# Heating_Controller.net
KiCad netlist of a schematic drawn in EAGLE
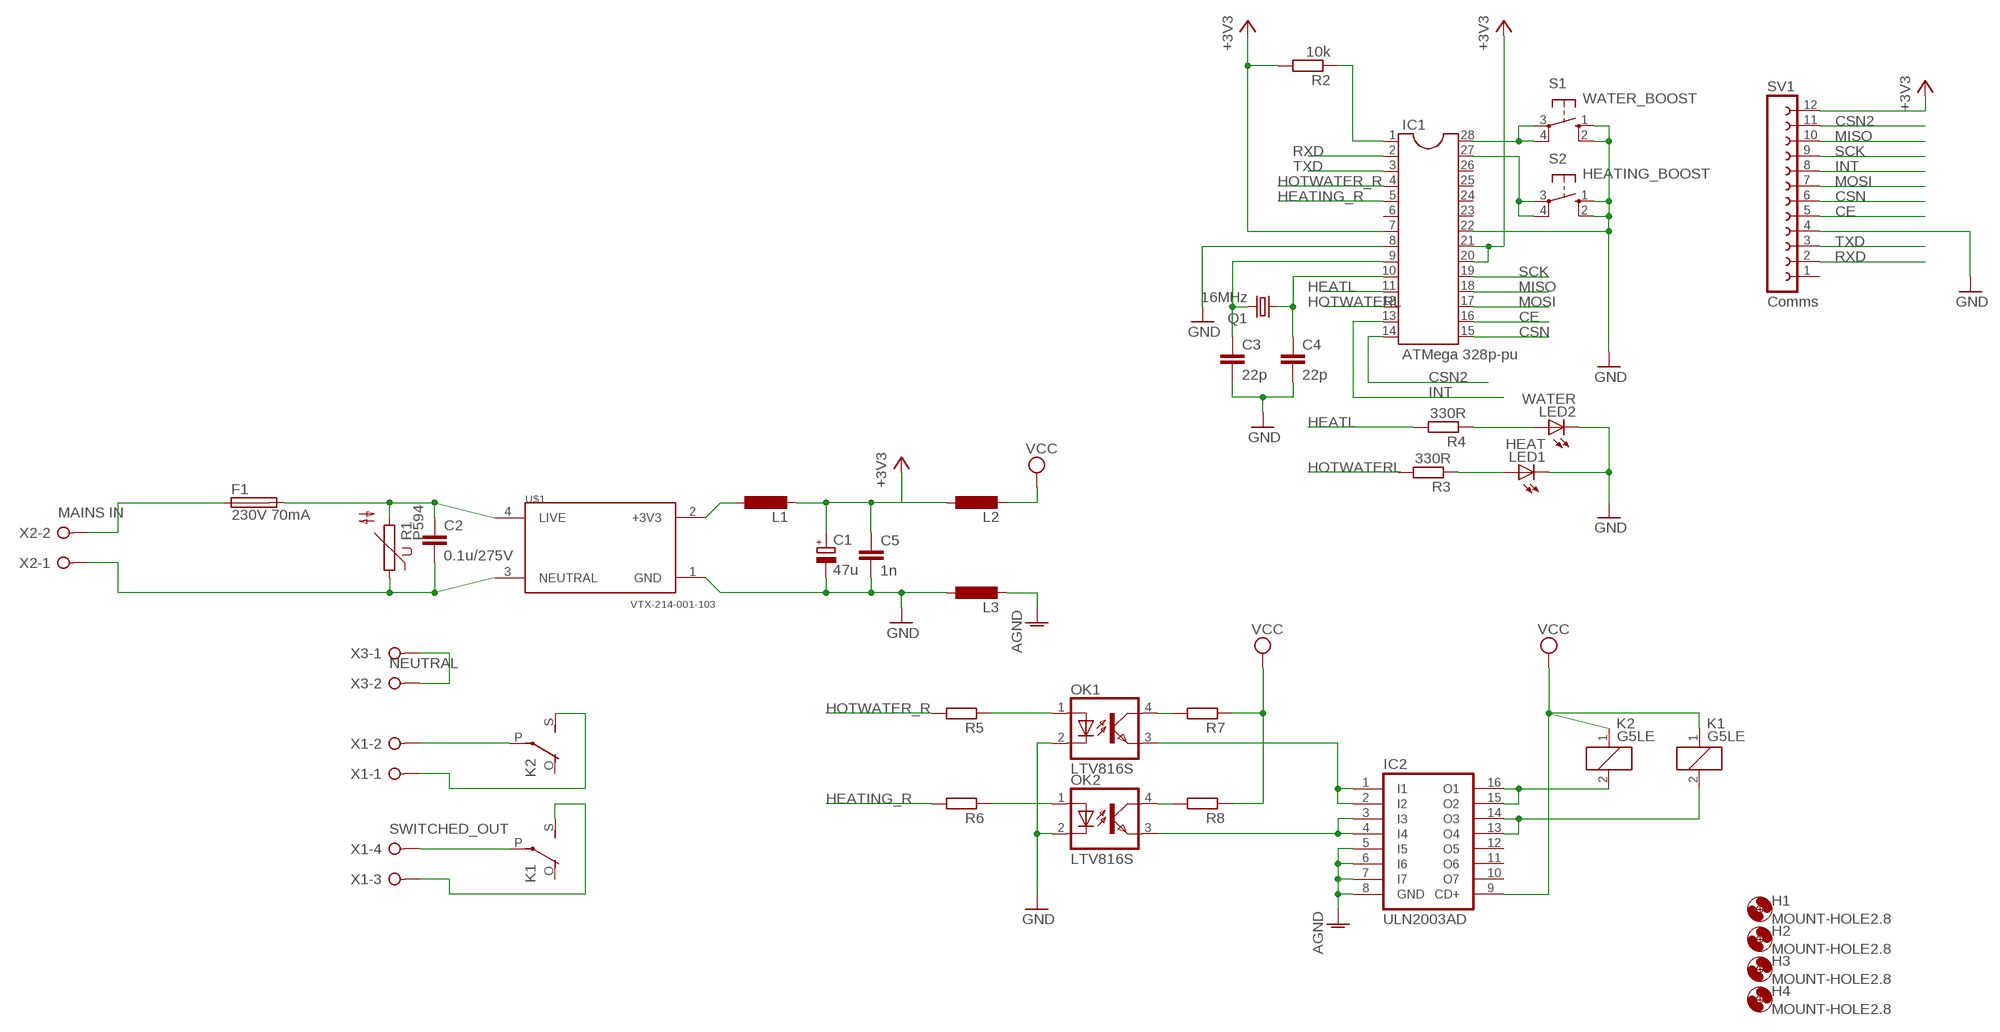
[diagram p0: schematic, sheet 1]

(export (version "E")
  (design (tool "Eeschema 10.0.6"))
  (components
    (comp (ref "C1")
      (value "47u")
      (footprint "eagle-import:E2,5-7")
      (libsource (lib "eagle-import") (part "CPOL-EUE2.5-7"))
    )
    (comp (ref "C2")
      (value "0.1u/275V")
      (footprint "eagle-import:C15B5")
      (libsource (lib "eagle-import") (part "C15/5"))
    )
    (comp (ref "C3")
      (value "22p")
      (footprint "eagle-import:C1206K")
      (libsource (lib "eagle-import") (part "C-EUC1206K"))
    )
    (comp (ref "C4")
      (value "22p")
      (footprint "eagle-import:C1206K")
      (libsource (lib "eagle-import") (part "C-EUC1206K"))
    )
    (comp (ref "C5")
      (value "1n")
      (footprint "eagle-import:C1206K")
      (libsource (lib "eagle-import") (part "C-EUC1206K"))
    )
    (comp (ref "F1")
      (value "230V 70mA")
      (footprint "eagle-import:SH22,5A")
      (fields (field (name "MPN") "0031.7701.11"))
      (libsource (lib "eagle-import") (part "SH22,5A"))
    )
    (comp (ref "H1")
      (value "MOUNT-HOLE2.8")
      (footprint "eagle-import:2,8")
      (libsource (lib "eagle-import") (part "MOUNT-HOLE2.8"))
    )
    (comp (ref "H2")
      (value "MOUNT-HOLE2.8")
      (footprint "eagle-import:2,8")
      (libsource (lib "eagle-import") (part "MOUNT-HOLE2.8"))
    )
    (comp (ref "H3")
      (value "MOUNT-HOLE2.8")
      (footprint "eagle-import:2,8")
      (libsource (lib "eagle-import") (part "MOUNT-HOLE2.8"))
    )
    (comp (ref "H4")
      (value "MOUNT-HOLE2.8")
      (footprint "eagle-import:2,8")
      (libsource (lib "eagle-import") (part "MOUNT-HOLE2.8"))
    )
    (comp (ref "IC1")
      (value "ATMega 328p-pu")
      (footprint "eagle-import:DIL28-3")
      (libsource (lib "eagle-import") (part "DIL28-3"))
    )
    (comp (ref "IC2")
      (value "ULN2003AD")
      (footprint "eagle-import:SO16")
      (libsource (lib "eagle-import") (part "ULN2003AD"))
    )
    (comp (ref "K1")
      (value "G5LE")
      (footprint "eagle-import:G5LE")
      (libsource (lib "eagle-import") (part "G5LE"))
    )
    (comp (ref "K2")
      (value "G5LE")
      (footprint "eagle-import:G5LE")
      (libsource (lib "eagle-import") (part "G5LE"))
    )
    (comp (ref "L1")
      (value "L-EUL3230M")
      (footprint "eagle-import:L3230M")
      (libsource (lib "eagle-import") (part "L-EUL3230M"))
    )
    (comp (ref "L2")
      (value "L-EUL3230M")
      (footprint "eagle-import:L3230M")
      (libsource (lib "eagle-import") (part "L-EUL3230M"))
    )
    (comp (ref "L3")
      (value "L-EUL3230M")
      (footprint "eagle-import:L3230M")
      (libsource (lib "eagle-import") (part "L-EUL3230M"))
    )
    (comp (ref "LED1")
      (value "HEAT")
      (footprint "eagle-import:LED5MM")
      (libsource (lib "eagle-import") (part "LED5MM"))
    )
    (comp (ref "LED2")
      (value "WATER")
      (footprint "eagle-import:LED5MM")
      (libsource (lib "eagle-import") (part "LED5MM"))
    )
    (comp (ref "OK1")
      (value "LTV816S")
      (footprint "eagle-import:SMD4")
      (libsource (lib "eagle-import") (part "LTV816S"))
    )
    (comp (ref "OK2")
      (value "LTV816S")
      (footprint "eagle-import:SMD4")
      (libsource (lib "eagle-import") (part "LTV816S"))
    )
    (comp (ref "Q1")
      (value "16MHz")
      (footprint "eagle-import:HC49_S")
      (libsource (lib "eagle-import") (part "CRYSTALHC49S"))
    )
    (comp (ref "R1")
      (value "P594")
      (footprint "eagle-import:P594")
      (libsource (lib "eagle-import") (part "P594"))
    )
    (comp (ref "R2")
      (value "10k")
      (footprint "eagle-import:R1206")
      (libsource (lib "eagle-import") (part "R-EU_R1206"))
    )
    (comp (ref "R3")
      (value "330R")
      (footprint "eagle-import:R1206")
      (libsource (lib "eagle-import") (part "R-EU_R1206"))
    )
    (comp (ref "R4")
      (value "330R")
      (footprint "eagle-import:R1206")
      (libsource (lib "eagle-import") (part "R-EU_R1206"))
    )
    (comp (ref "R5")
      (value "R-EU_R1206")
      (footprint "eagle-import:R1206")
      (libsource (lib "eagle-import") (part "R-EU_R1206"))
    )
    (comp (ref "R6")
      (value "R-EU_R1206")
      (footprint "eagle-import:R1206")
      (libsource (lib "eagle-import") (part "R-EU_R1206"))
    )
    (comp (ref "R7")
      (value "R-EU_R1206")
      (footprint "eagle-import:R1206")
      (libsource (lib "eagle-import") (part "R-EU_R1206"))
    )
    (comp (ref "R8")
      (value "R-EU_R1206")
      (footprint "eagle-import:R1206")
      (libsource (lib "eagle-import") (part "R-EU_R1206"))
    )
    (comp (ref "S1")
      (value "WATER_BOOST")
      (footprint "eagle-import:B3F-40XX")
      (fields (field (name "MF") "OMRON COMPONENTS USA") (field (name "MPN") "B3F-4000"))
      (libsource (lib "eagle-import") (part "40-XX"))
    )
    (comp (ref "S2")
      (value "HEATING_BOOST")
      (footprint "eagle-import:B3F-40XX")
      (fields (field (name "MF") "OMRON COMPONENTS USA") (field (name "MPN") "B3F-4000"))
      (libsource (lib "eagle-import") (part "40-XX"))
    )
    (comp (ref "SV1")
      (value "Comms")
      (footprint "eagle-import:FE12W")
      (libsource (lib "eagle-import") (part "FE12W"))
    )
    (comp (ref "U$1")
      (value "VTX-214-001-103")
      (footprint "eagle-import:VTX214001103")
      (libsource (lib "eagle-import") (part "VTX-214-001-103"))
    )
    (comp (ref "X1")
      (value "SWITCHED_OUT")
      (footprint "eagle-import:W237-4P")
      (libsource (lib "eagle-import") (part "W237-04P"))
    )
    (comp (ref "X2")
      (value "MAINS IN")
      (footprint "eagle-import:W237-132")
      (libsource (lib "eagle-import") (part "W237-02P"))
    )
    (comp (ref "X3")
      (value "NEUTRAL")
      (footprint "eagle-import:W237-132")
      (libsource (lib "eagle-import") (part "W237-02P"))
    )
  )
  (nets
    (net (code "1") (name "+3V3") (class "Default")
      (node (ref "C1") (pin "+") (pinfunction "+_+") (pintype "passive"))
      (node (ref "C5") (pin "1") (pinfunction "1_1") (pintype "passive"))
      (node (ref "IC1") (pin "20") (pinfunction "20_20") (pintype "passive"))
      (node (ref "IC1") (pin "21") (pinfunction "21_21") (pintype "passive"))
      (node (ref "IC1") (pin "7") (pinfunction "7_7") (pintype "passive"))
      (node (ref "L1") (pin "2") (pinfunction "2_2") (pintype "passive"))
      (node (ref "L2") (pin "1") (pinfunction "1_1") (pintype "passive"))
      (node (ref "R2") (pin "2") (pinfunction "2_2") (pintype "passive"))
      (node (ref "SV1") (pin "12") (pinfunction "12_12") (pintype "passive"))
    )
    (net (code "2") (name "/CE") (class "Default")
      (node (ref "IC1") (pin "16") (pinfunction "16_16") (pintype "passive"))
      (node (ref "SV1") (pin "5") (pinfunction "5_5") (pintype "passive"))
    )
    (net (code "3") (name "/CSN") (class "Default")
      (node (ref "IC1") (pin "15") (pinfunction "15_15") (pintype "passive"))
      (node (ref "SV1") (pin "6") (pinfunction "6_6") (pintype "passive"))
    )
    (net (code "4") (name "/CSN2") (class "Default")
      (node (ref "IC1") (pin "14") (pinfunction "14_14") (pintype "passive"))
      (node (ref "SV1") (pin "11") (pinfunction "11_11") (pintype "passive"))
    )
    (net (code "5") (name "/HEATING_R") (class "Default")
      (node (ref "IC1") (pin "5") (pinfunction "5_5") (pintype "passive"))
      (node (ref "R6") (pin "2") (pinfunction "2_2") (pintype "passive"))
    )
    (net (code "6") (name "/HEATL") (class "Default")
      (node (ref "IC1") (pin "11") (pinfunction "11_11") (pintype "passive"))
      (node (ref "R4") (pin "2") (pinfunction "2_2") (pintype "passive"))
    )
    (net (code "7") (name "/HOTWATERL") (class "Default")
      (node (ref "IC1") (pin "12") (pinfunction "12_12") (pintype "passive"))
      (node (ref "R3") (pin "2") (pinfunction "2_2") (pintype "passive"))
    )
    (net (code "8") (name "/HOTWATER_R") (class "Default")
      (node (ref "IC1") (pin "4") (pinfunction "4_4") (pintype "passive"))
      (node (ref "R5") (pin "2") (pinfunction "2_2") (pintype "passive"))
    )
    (net (code "9") (name "/INT") (class "Default")
      (node (ref "IC1") (pin "13") (pinfunction "13_13") (pintype "passive"))
      (node (ref "SV1") (pin "8") (pinfunction "8_8") (pintype "passive"))
    )
    (net (code "10") (name "/MISO") (class "Default")
      (node (ref "IC1") (pin "18") (pinfunction "18_18") (pintype "passive"))
      (node (ref "SV1") (pin "10") (pinfunction "10_10") (pintype "passive"))
    )
    (net (code "11") (name "/MOSI") (class "Default")
      (node (ref "IC1") (pin "17") (pinfunction "17_17") (pintype "passive"))
      (node (ref "SV1") (pin "7") (pinfunction "7_7") (pintype "passive"))
    )
    (net (code "12") (name "/RXD") (class "Default")
      (node (ref "IC1") (pin "2") (pinfunction "2_2") (pintype "passive"))
      (node (ref "SV1") (pin "2") (pinfunction "2_2") (pintype "passive"))
    )
    (net (code "13") (name "/SCK") (class "Default")
      (node (ref "IC1") (pin "19") (pinfunction "19_19") (pintype "passive"))
      (node (ref "SV1") (pin "9") (pinfunction "9_9") (pintype "passive"))
    )
    (net (code "14") (name "/TXD") (class "Default")
      (node (ref "IC1") (pin "3") (pinfunction "3_3") (pintype "passive"))
      (node (ref "SV1") (pin "3") (pinfunction "3_3") (pintype "passive"))
    )
    (net (code "15") (name "AGND") (class "Default")
      (node (ref "IC2") (pin "5") (pinfunction "I5_5") (pintype "input"))
      (node (ref "IC2") (pin "6") (pinfunction "I6_6") (pintype "input"))
      (node (ref "IC2") (pin "7") (pinfunction "I7_7") (pintype "input"))
      (node (ref "IC2") (pin "8") (pinfunction "GND_8") (pintype "power_in"))
      (node (ref "L3") (pin "2") (pinfunction "2_2") (pintype "passive"))
    )
    (net (code "16") (name "GND") (class "Default")
      (node (ref "C1") (pin "-") (pinfunction "-_-") (pintype "passive"))
      (node (ref "C3") (pin "2") (pinfunction "2_2") (pintype "passive"))
      (node (ref "C4") (pin "2") (pinfunction "2_2") (pintype "passive"))
      (node (ref "C5") (pin "2") (pinfunction "2_2") (pintype "passive"))
      (node (ref "IC1") (pin "22") (pinfunction "22_22") (pintype "passive"))
      (node (ref "IC1") (pin "8") (pinfunction "8_8") (pintype "passive"))
      (node (ref "L3") (pin "1") (pinfunction "1_1") (pintype "passive"))
      (node (ref "LED1") (pin "K") (pinfunction "C_K") (pintype "passive"))
      (node (ref "LED2") (pin "K") (pinfunction "C_K") (pintype "passive"))
      (node (ref "OK1") (pin "2") (pinfunction "C_2") (pintype "passive"))
      (node (ref "OK2") (pin "2") (pinfunction "C_2") (pintype "passive"))
      (node (ref "S1") (pin "1") (pinfunction "S_1") (pintype "passive"))
      (node (ref "S1") (pin "2") (pinfunction "S1_2") (pintype "passive"))
      (node (ref "S2") (pin "1") (pinfunction "S_1") (pintype "passive"))
      (node (ref "S2") (pin "2") (pinfunction "S1_2") (pintype "passive"))
      (node (ref "SV1") (pin "4") (pinfunction "4_4") (pintype "passive"))
      (node (ref "U$1") (pin "1") (pinfunction "GND_1") (pintype "power_in"))
    )
    (net (code "17") (name "Net-(C3-Pad1)") (class "Default")
      (node (ref "C3") (pin "1") (pinfunction "1_1") (pintype "passive"))
      (node (ref "IC1") (pin "9") (pinfunction "9_9") (pintype "passive"))
      (node (ref "Q1") (pin "2") (pinfunction "2_2") (pintype "passive"))
    )
    (net (code "18") (name "Net-(C4-Pad1)") (class "Default")
      (node (ref "C4") (pin "1") (pinfunction "1_1") (pintype "passive"))
      (node (ref "IC1") (pin "10") (pinfunction "10_10") (pintype "passive"))
      (node (ref "Q1") (pin "1") (pinfunction "1_1") (pintype "passive"))
    )
    (net (code "19") (name "Net-(IC1-Pad1)") (class "Default")
      (node (ref "IC1") (pin "1") (pinfunction "1_1") (pintype "passive"))
      (node (ref "R2") (pin "1") (pinfunction "1_1") (pintype "passive"))
    )
    (net (code "20") (name "Net-(IC2-I1)") (class "Default")
      (node (ref "IC2") (pin "1") (pinfunction "I1_1") (pintype "input"))
      (node (ref "IC2") (pin "2") (pinfunction "I2_2") (pintype "input"))
      (node (ref "OK1") (pin "3") (pinfunction "EMIT_3") (pintype "passive"))
    )
    (net (code "21") (name "Net-(IC2-I3)") (class "Default")
      (node (ref "IC2") (pin "3") (pinfunction "I3_3") (pintype "input"))
      (node (ref "IC2") (pin "4") (pinfunction "I4_4") (pintype "input"))
      (node (ref "OK2") (pin "3") (pinfunction "EMIT_3") (pintype "passive"))
    )
    (net (code "22") (name "Net-(IC2-O1)") (class "Default")
      (node (ref "IC2") (pin "15") (pinfunction "O2_15") (pintype "open_collector"))
      (node (ref "IC2") (pin "16") (pinfunction "O1_16") (pintype "open_collector"))
      (node (ref "K2") (pin "2") (pinfunction "2_2") (pintype "passive"))
    )
    (net (code "23") (name "Net-(IC2-O3)") (class "Default")
      (node (ref "IC2") (pin "13") (pinfunction "O4_13") (pintype "open_collector"))
      (node (ref "IC2") (pin "14") (pinfunction "O3_14") (pintype "open_collector"))
      (node (ref "K1") (pin "2") (pinfunction "2_2") (pintype "passive"))
    )
    (net (code "24") (name "Net-(LED1-PadA)") (class "Default")
      (node (ref "LED1") (pin "A") (pinfunction "A_A") (pintype "passive"))
      (node (ref "R3") (pin "1") (pinfunction "1_1") (pintype "passive"))
    )
    (net (code "25") (name "Net-(LED2-PadA)") (class "Default")
      (node (ref "LED2") (pin "A") (pinfunction "A_A") (pintype "passive"))
      (node (ref "R4") (pin "1") (pinfunction "1_1") (pintype "passive"))
    )
    (net (code "26") (name "Net-(OK1-A)") (class "Default")
      (node (ref "OK1") (pin "1") (pinfunction "A_1") (pintype "passive"))
      (node (ref "R5") (pin "1") (pinfunction "1_1") (pintype "passive"))
    )
    (net (code "27") (name "Net-(OK1-COL)") (class "Default")
      (node (ref "OK1") (pin "4") (pinfunction "COL_4") (pintype "passive"))
      (node (ref "R7") (pin "2") (pinfunction "2_2") (pintype "passive"))
    )
    (net (code "28") (name "Net-(OK2-A)") (class "Default")
      (node (ref "OK2") (pin "1") (pinfunction "A_1") (pintype "passive"))
      (node (ref "R6") (pin "1") (pinfunction "1_1") (pintype "passive"))
    )
    (net (code "29") (name "Net-(OK2-COL)") (class "Default")
      (node (ref "OK2") (pin "4") (pinfunction "COL_4") (pintype "passive"))
      (node (ref "R8") (pin "2") (pinfunction "2_2") (pintype "passive"))
    )
    (net (code "30") (name "Net-(S1-P)") (class "Default")
      (node (ref "IC1") (pin "28") (pinfunction "28_28") (pintype "passive"))
      (node (ref "S1") (pin "3") (pinfunction "P_3") (pintype "passive"))
      (node (ref "S1") (pin "4") (pinfunction "P1_4") (pintype "passive"))
    )
    (net (code "31") (name "Net-(S2-P)") (class "Default")
      (node (ref "IC1") (pin "27") (pinfunction "27_27") (pintype "passive"))
      (node (ref "S2") (pin "3") (pinfunction "P_3") (pintype "passive"))
      (node (ref "S2") (pin "4") (pinfunction "P1_4") (pintype "passive"))
    )
    (net (code "32") (name "Net-(U$1-+3V3)") (class "Default")
      (node (ref "L1") (pin "1") (pinfunction "1_1") (pintype "passive"))
      (node (ref "U$1") (pin "2") (pinfunction "+3V3_2") (pintype "power_in"))
    )
    (net (code "33") (name "Net-(U$1-LIVE)") (class "Default")
      (node (ref "C2") (pin "1") (pinfunction "1_1") (pintype "passive"))
      (node (ref "F1") (pin "2") (pinfunction "2_2") (pintype "passive"))
      (node (ref "R1") (pin "2") (pinfunction "2_2") (pintype "passive"))
      (node (ref "U$1") (pin "4") (pinfunction "LIVE_4") (pintype "input"))
    )
    (net (code "34") (name "Net-(U$1-NEUTRAL)") (class "Default")
      (node (ref "C2") (pin "2") (pinfunction "2_2") (pintype "passive"))
      (node (ref "R1") (pin "1") (pinfunction "1_1") (pintype "passive"))
      (node (ref "U$1") (pin "3") (pinfunction "NEUTRAL_3") (pintype "input"))
      (node (ref "X2") (pin "1") (pinfunction "KL_1") (pintype "passive"))
    )
    (net (code "35") (name "Net-(X1A-KL)") (class "Default")
      (node (ref "K2") (pin "S") (pinfunction "S_S") (pintype "passive"))
      (node (ref "X1") (pin "1") (pinfunction "KL_1") (pintype "passive"))
    )
    (net (code "36") (name "Net-(X1B-KL)") (class "Default")
      (node (ref "K2") (pin "P") (pinfunction "P_P") (pintype "passive"))
      (node (ref "X1") (pin "2") (pinfunction "KL_2") (pintype "passive"))
    )
    (net (code "37") (name "Net-(X1C-KL)") (class "Default")
      (node (ref "K1") (pin "S") (pinfunction "S_S") (pintype "passive"))
      (node (ref "X1") (pin "3") (pinfunction "KL_3") (pintype "passive"))
    )
    (net (code "38") (name "Net-(X1D-KL)") (class "Default")
      (node (ref "K1") (pin "P") (pinfunction "P_P") (pintype "passive"))
      (node (ref "X1") (pin "4") (pinfunction "KL_4") (pintype "passive"))
    )
    (net (code "39") (name "Net-(X2B-KL)") (class "Default")
      (node (ref "F1") (pin "1") (pinfunction "1_1") (pintype "passive"))
      (node (ref "X2") (pin "2") (pinfunction "KL_2") (pintype "passive"))
    )
    (net (code "40") (name "Net-(X3A-KL)") (class "Default")
      (node (ref "X3") (pin "1") (pinfunction "KL_1") (pintype "passive"))
      (node (ref "X3") (pin "2") (pinfunction "KL_2") (pintype "passive"))
    )
    (net (code "41") (name "VCC") (class "Default")
      (node (ref "IC2") (pin "9") (pinfunction "CD+_9") (pintype "passive"))
      (node (ref "K1") (pin "1") (pinfunction "1_1") (pintype "passive"))
      (node (ref "K2") (pin "1") (pinfunction "1_1") (pintype "passive"))
      (node (ref "L2") (pin "2") (pinfunction "2_2") (pintype "passive"))
      (node (ref "R7") (pin "1") (pinfunction "1_1") (pintype "passive"))
      (node (ref "R8") (pin "1") (pinfunction "1_1") (pintype "passive"))
    )
    (net (code "42") (name "unconnected-(IC1-Pad6)") (class "Default")
      (node (ref "IC1") (pin "6") (pinfunction "6_6") (pintype "passive"))
    )
    (net (code "43") (name "unconnected-(IC1-Pad23)") (class "Default")
      (node (ref "IC1") (pin "23") (pinfunction "23_23") (pintype "passive"))
    )
    (net (code "44") (name "unconnected-(IC1-Pad24)") (class "Default")
      (node (ref "IC1") (pin "24") (pinfunction "24_24") (pintype "passive"))
    )
    (net (code "45") (name "unconnected-(IC1-Pad25)") (class "Default")
      (node (ref "IC1") (pin "25") (pinfunction "25_25") (pintype "passive"))
    )
    (net (code "46") (name "unconnected-(IC1-Pad26)") (class "Default")
      (node (ref "IC1") (pin "26") (pinfunction "26_26") (pintype "passive"))
    )
    (net (code "47") (name "unconnected-(IC2-O5-Pad12)") (class "Default")
      (node (ref "IC2") (pin "12") (pinfunction "O5_12") (pintype "open_collector"))
    )
    (net (code "48") (name "unconnected-(IC2-O6-Pad11)") (class "Default")
      (node (ref "IC2") (pin "11") (pinfunction "O6_11") (pintype "open_collector"))
    )
    (net (code "49") (name "unconnected-(IC2-O7-Pad10)") (class "Default")
      (node (ref "IC2") (pin "10") (pinfunction "O7_10") (pintype "open_collector"))
    )
    (net (code "50") (name "unconnected-(K1-PadO)") (class "Default")
      (node (ref "K1") (pin "O") (pinfunction "O_O") (pintype "passive"))
    )
    (net (code "51") (name "unconnected-(K2-PadO)") (class "Default")
      (node (ref "K2") (pin "O") (pinfunction "O_O") (pintype "passive"))
    )
    (net (code "52") (name "unconnected-(SV1-Pad1)") (class "Default")
      (node (ref "SV1") (pin "1") (pinfunction "1_1") (pintype "passive"))
    )
  )
)
